# harkled.net
KiCad netlist of a schematic drawn in EAGLE
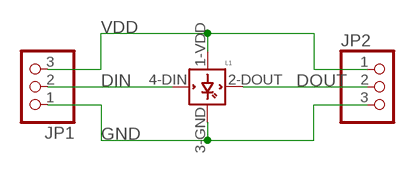
[diagram p0: schematic, sheet 1]

(export (version "E")
  (design (tool "Eeschema 10.0.6"))
  (components
    (comp (ref "JP1")
      (value "PINHD-1X3")
      (footprint "eagle-import:1X03")
      (libsource (lib "eagle-import") (part "PINHD-1X3"))
    )
    (comp (ref "JP2")
      (value "PINHD-1X3")
      (footprint "eagle-import:1X03")
      (libsource (lib "eagle-import") (part "PINHD-1X3"))
    )
    (comp (ref "L1")
      (value "WS2812B")
      (footprint "eagle-import:WS2812B")
      (libsource (lib "eagle-import") (part "WS2812B"))
    )
  )
  (nets
    (net (code "1") (name "/DIN") (class "Default")
      (node (ref "JP1") (pin "2") (pinfunction "2_2") (pintype "passive"))
      (node (ref "L1") (pin "4-DIN") (pinfunction "DIN_4-DIN") (pintype "input"))
    )
    (net (code "2") (name "/DOUT") (class "Default")
      (node (ref "JP2") (pin "2") (pinfunction "2_2") (pintype "passive"))
      (node (ref "L1") (pin "2-DOUT") (pinfunction "DOUT_2-DOUT") (pintype "output"))
    )
    (net (code "3") (name "/GND") (class "Default")
      (node (ref "JP1") (pin "1") (pinfunction "1_1") (pintype "passive"))
      (node (ref "JP2") (pin "3") (pinfunction "3_3") (pintype "passive"))
      (node (ref "L1") (pin "3-GND") (pinfunction "GND_3-GND") (pintype "bidirectional"))
    )
    (net (code "4") (name "/VDD") (class "Default")
      (node (ref "JP1") (pin "3") (pinfunction "3_3") (pintype "passive"))
      (node (ref "JP2") (pin "1") (pinfunction "1_1") (pintype "passive"))
      (node (ref "L1") (pin "1-VDD") (pinfunction "VDD_1-VDD") (pintype "bidirectional"))
    )
  )
)
